# Connectors_MILSPEC.net
KiCad netlist of a schematic drawn in Altium Designer
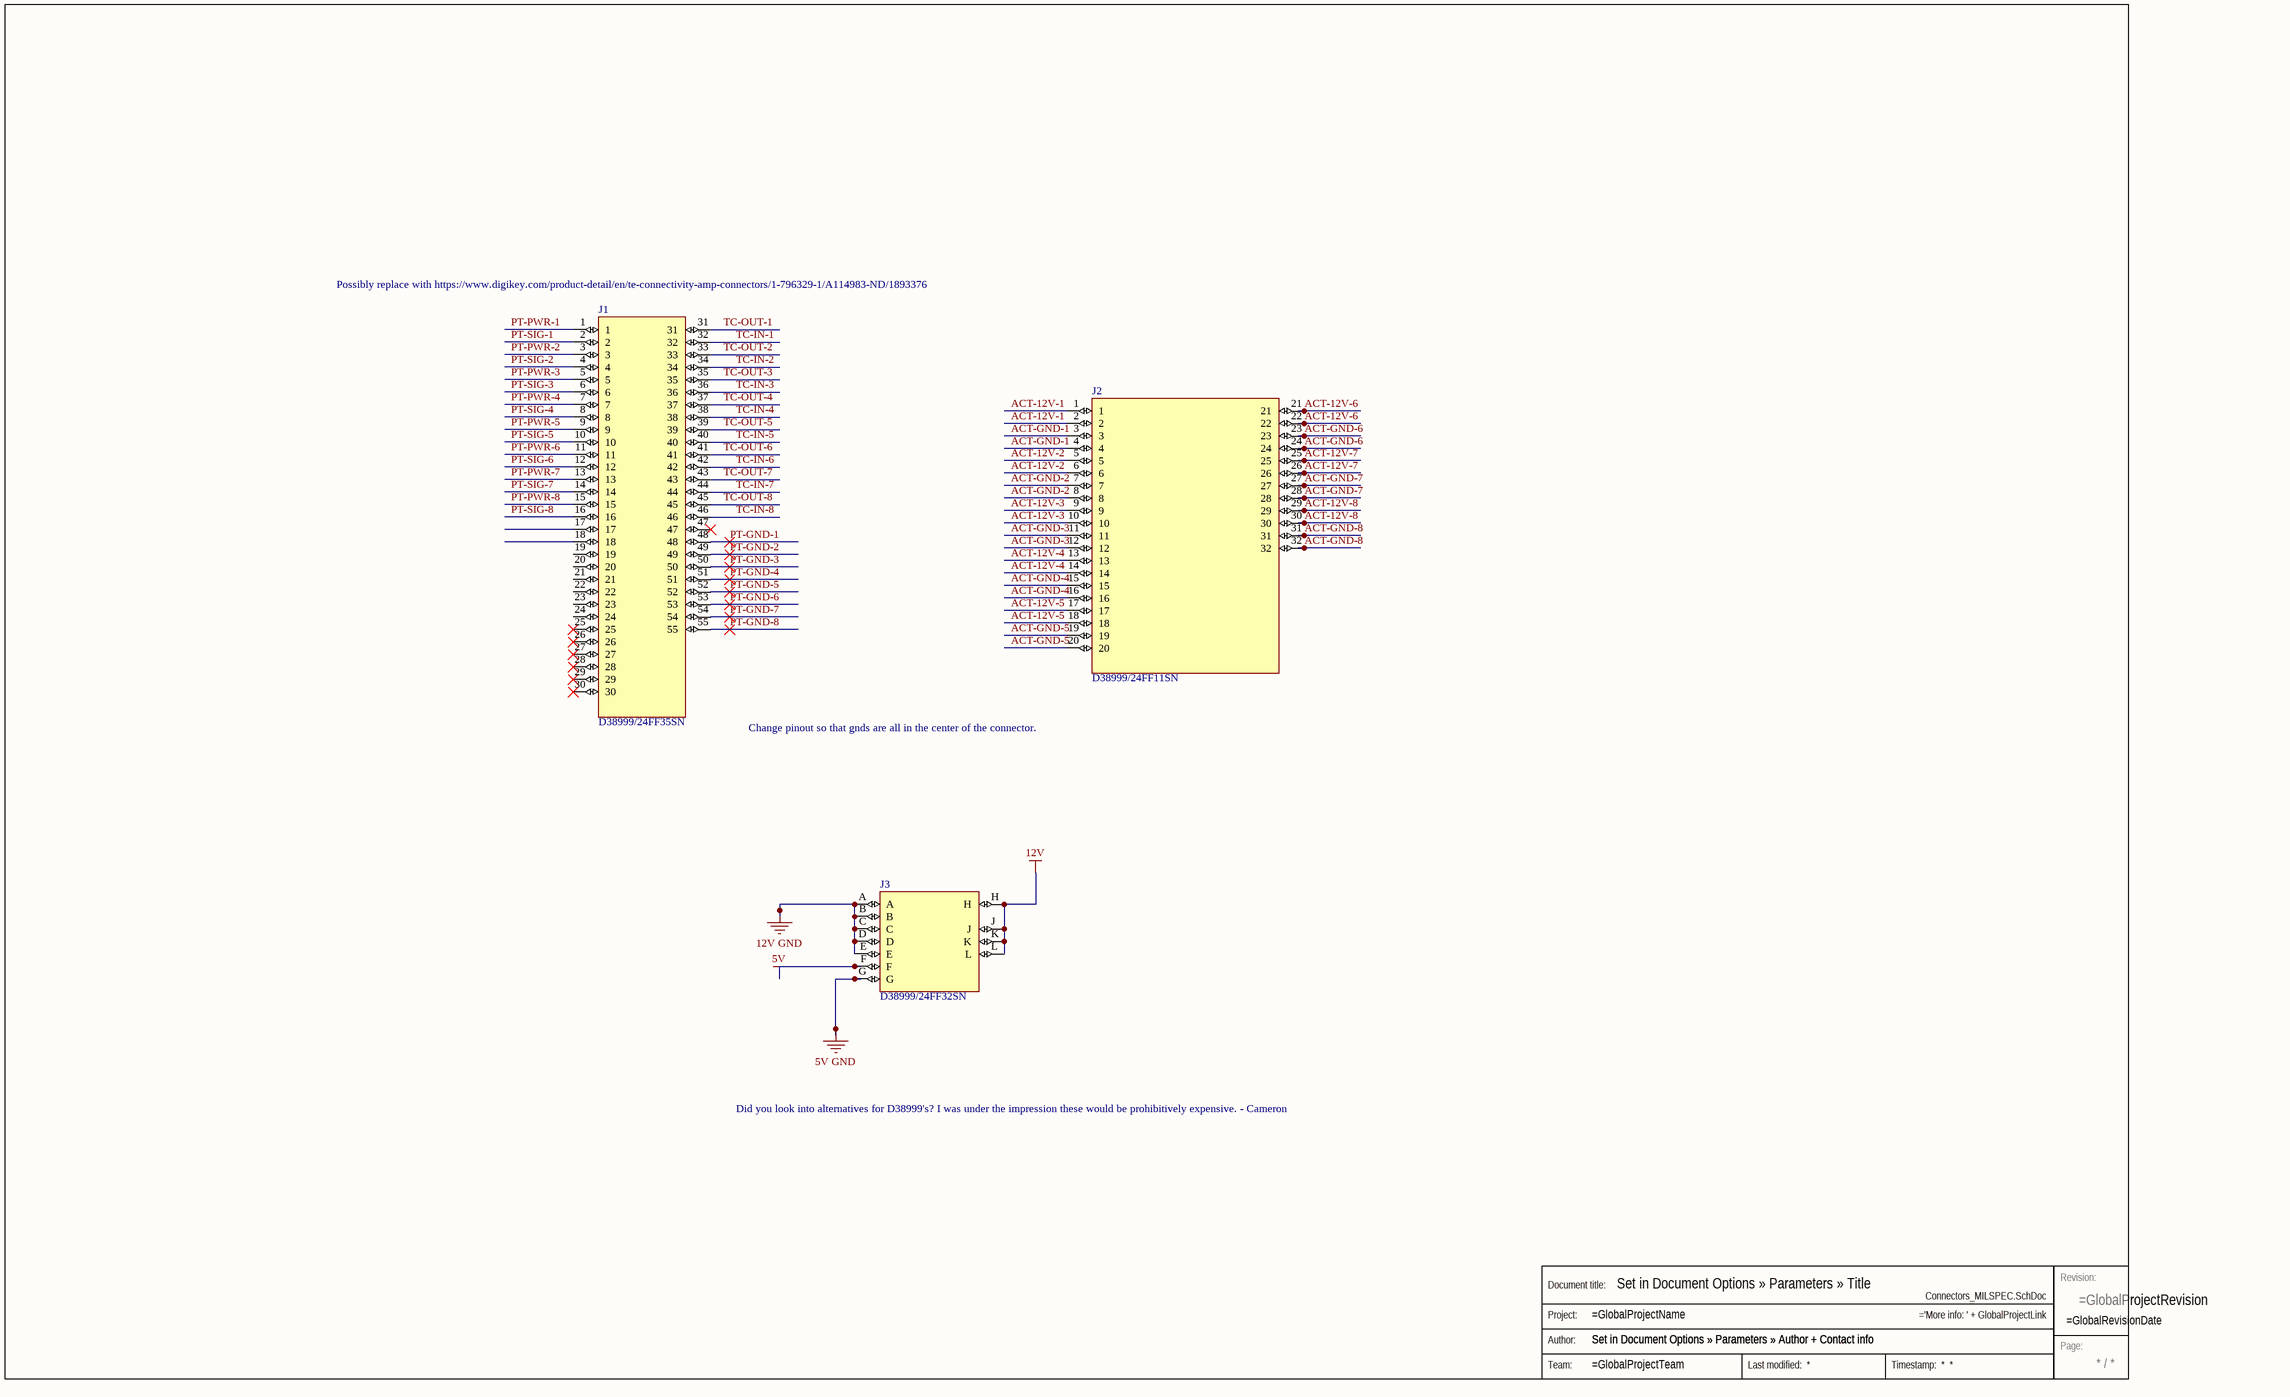
[diagram p0: Connectors_MILSPEC.SchDoc]

(export (version "E")
  (design (tool "Eeschema 10.0.6"))
  (components
    (comp (ref "J1")
      (value "D38999/24FF35SN")
      (footprint "17-35")
      (description "D38999/24FE35SN")
      (libsource (lib "D38999 connectors") (part "D38999/24FF35SN"))
    )
    (comp (ref "J2")
      (value "D38999/24FF11SN")
      (footprint "19-32")
      (libsource (lib "D38999 connectors") (part "D38999/24FF11SN"))
    )
    (comp (ref "J3")
      (value "D38999/24FF32SN")
      (footprint "19-11")
      (libsource (lib "D38999 connectors") (part "D38999/24FF32SN"))
    )
    (comp (ref "Stamp") (value "Stamp") (libsource (lib "ShieldsLib") (part "Stamp")))
  )
  (nets
    (net (code "1") (name "/ACT-12V-1") (class "Default")
      (node (ref "J2") (pin "1") (pinfunction "1_1") (pintype "bidirectional"))
      (node (ref "J2") (pin "2") (pinfunction "2_2") (pintype "bidirectional"))
    )
    (net (code "2") (name "/ACT-12V-2") (class "Default")
      (node (ref "J2") (pin "5") (pinfunction "5_5") (pintype "bidirectional"))
      (node (ref "J2") (pin "6") (pinfunction "6_6") (pintype "bidirectional"))
    )
    (net (code "3") (name "/ACT-12V-3") (class "Default")
      (node (ref "J2") (pin "10") (pinfunction "10_10") (pintype "bidirectional"))
      (node (ref "J2") (pin "9") (pinfunction "9_9") (pintype "bidirectional"))
    )
    (net (code "4") (name "/ACT-12V-4") (class "Default")
      (node (ref "J2") (pin "13") (pinfunction "13_13") (pintype "bidirectional"))
      (node (ref "J2") (pin "14") (pinfunction "14_14") (pintype "bidirectional"))
    )
    (net (code "5") (name "/ACT-12V-5") (class "Default")
      (node (ref "J2") (pin "17") (pinfunction "17_17") (pintype "bidirectional"))
      (node (ref "J2") (pin "18") (pinfunction "18_18") (pintype "bidirectional"))
    )
    (net (code "6") (name "/ACT-12V-6") (class "Default")
      (node (ref "J2") (pin "21") (pinfunction "21_21") (pintype "bidirectional"))
      (node (ref "J2") (pin "22") (pinfunction "22_22") (pintype "bidirectional"))
    )
    (net (code "7") (name "/ACT-12V-7") (class "Default")
      (node (ref "J2") (pin "25") (pinfunction "25_25") (pintype "bidirectional"))
      (node (ref "J2") (pin "26") (pinfunction "26_26") (pintype "bidirectional"))
    )
    (net (code "8") (name "/ACT-12V-8") (class "Default")
      (node (ref "J2") (pin "29") (pinfunction "29_29") (pintype "bidirectional"))
      (node (ref "J2") (pin "30") (pinfunction "30_30") (pintype "bidirectional"))
    )
    (net (code "9") (name "/ACT-GND-1") (class "Default")
      (node (ref "J2") (pin "3") (pinfunction "3_3") (pintype "bidirectional"))
      (node (ref "J2") (pin "4") (pinfunction "4_4") (pintype "bidirectional"))
    )
    (net (code "10") (name "/ACT-GND-2") (class "Default")
      (node (ref "J2") (pin "7") (pinfunction "7_7") (pintype "bidirectional"))
      (node (ref "J2") (pin "8") (pinfunction "8_8") (pintype "bidirectional"))
    )
    (net (code "11") (name "/ACT-GND-3") (class "Default")
      (node (ref "J2") (pin "11") (pinfunction "11_11") (pintype "bidirectional"))
      (node (ref "J2") (pin "12") (pinfunction "12_12") (pintype "bidirectional"))
    )
    (net (code "12") (name "/ACT-GND-4") (class "Default")
      (node (ref "J2") (pin "15") (pinfunction "15_15") (pintype "bidirectional"))
      (node (ref "J2") (pin "16") (pinfunction "16_16") (pintype "bidirectional"))
    )
    (net (code "13") (name "/ACT-GND-5") (class "Default")
      (node (ref "J2") (pin "19") (pinfunction "19_19") (pintype "bidirectional"))
      (node (ref "J2") (pin "20") (pinfunction "20_20") (pintype "bidirectional"))
    )
    (net (code "14") (name "/ACT-GND-6") (class "Default")
      (node (ref "J2") (pin "23") (pinfunction "23_23") (pintype "bidirectional"))
      (node (ref "J2") (pin "24") (pinfunction "24_24") (pintype "bidirectional"))
    )
    (net (code "15") (name "/ACT-GND-7") (class "Default")
      (node (ref "J2") (pin "27") (pinfunction "27_27") (pintype "bidirectional"))
      (node (ref "J2") (pin "28") (pinfunction "28_28") (pintype "bidirectional"))
    )
    (net (code "16") (name "/ACT-GND-8") (class "Default")
      (node (ref "J2") (pin "31") (pinfunction "31_31") (pintype "bidirectional"))
      (node (ref "J2") (pin "32") (pinfunction "32_32") (pintype "bidirectional"))
    )
    (net (code "25") (name "/PT-GND-1") (class "Default")
      (node (ref "J1") (pin "48") (pinfunction "48_48") (pintype "bidirectional"))
    )
    (net (code "26") (name "/PT-GND-2") (class "Default")
      (node (ref "J1") (pin "49") (pinfunction "49_49") (pintype "bidirectional"))
    )
    (net (code "27") (name "/PT-GND-3") (class "Default")
      (node (ref "J1") (pin "50") (pinfunction "50_50") (pintype "bidirectional"))
    )
    (net (code "28") (name "/PT-GND-4") (class "Default")
      (node (ref "J1") (pin "51") (pinfunction "51_51") (pintype "bidirectional"))
    )
    (net (code "29") (name "/PT-GND-5") (class "Default")
      (node (ref "J1") (pin "52") (pinfunction "52_52") (pintype "bidirectional"))
    )
    (net (code "30") (name "/PT-GND-6") (class "Default")
      (node (ref "J1") (pin "53") (pinfunction "53_53") (pintype "bidirectional"))
    )
    (net (code "31") (name "/PT-GND-7") (class "Default")
      (node (ref "J1") (pin "54") (pinfunction "54_54") (pintype "bidirectional"))
    )
    (net (code "32") (name "/PT-GND-8") (class "Default")
      (node (ref "J1") (pin "55") (pinfunction "55_55") (pintype "bidirectional"))
    )
    (net (code "33") (name "/PT-PWR-1") (class "Default")
      (node (ref "J1") (pin "1") (pinfunction "1_1") (pintype "bidirectional"))
    )
    (net (code "34") (name "/PT-PWR-2") (class "Default")
      (node (ref "J1") (pin "3") (pinfunction "3_3") (pintype "bidirectional"))
    )
    (net (code "35") (name "/PT-PWR-3") (class "Default")
      (node (ref "J1") (pin "5") (pinfunction "5_5") (pintype "bidirectional"))
    )
    (net (code "36") (name "/PT-PWR-4") (class "Default")
      (node (ref "J1") (pin "7") (pinfunction "7_7") (pintype "bidirectional"))
    )
    (net (code "37") (name "/PT-PWR-5") (class "Default")
      (node (ref "J1") (pin "9") (pinfunction "9_9") (pintype "bidirectional"))
    )
    (net (code "38") (name "/PT-PWR-6") (class "Default")
      (node (ref "J1") (pin "11") (pinfunction "11_11") (pintype "bidirectional"))
    )
    (net (code "39") (name "/PT-PWR-7") (class "Default")
      (node (ref "J1") (pin "13") (pinfunction "13_13") (pintype "bidirectional"))
    )
    (net (code "40") (name "/PT-PWR-8") (class "Default")
      (node (ref "J1") (pin "15") (pinfunction "15_15") (pintype "bidirectional"))
    )
    (net (code "41") (name "/PT-SIG-1") (class "Default")
      (node (ref "J1") (pin "2") (pinfunction "2_2") (pintype "bidirectional"))
    )
    (net (code "42") (name "/PT-SIG-2") (class "Default")
      (node (ref "J1") (pin "4") (pinfunction "4_4") (pintype "bidirectional"))
    )
    (net (code "43") (name "/PT-SIG-3") (class "Default")
      (node (ref "J1") (pin "6") (pinfunction "6_6") (pintype "bidirectional"))
    )
    (net (code "44") (name "/PT-SIG-4") (class "Default")
      (node (ref "J1") (pin "8") (pinfunction "8_8") (pintype "bidirectional"))
    )
    (net (code "45") (name "/PT-SIG-5") (class "Default")
      (node (ref "J1") (pin "10") (pinfunction "10_10") (pintype "bidirectional"))
    )
    (net (code "46") (name "/PT-SIG-6") (class "Default")
      (node (ref "J1") (pin "12") (pinfunction "12_12") (pintype "bidirectional"))
    )
    (net (code "47") (name "/PT-SIG-7") (class "Default")
      (node (ref "J1") (pin "14") (pinfunction "14_14") (pintype "bidirectional"))
    )
    (net (code "48") (name "/PT-SIG-8") (class "Default")
      (node (ref "J1") (pin "16") (pinfunction "16_16") (pintype "bidirectional"))
    )
    (net (code "49") (name "/TC-IN-1") (class "Default")
      (node (ref "J1") (pin "32") (pinfunction "32_32") (pintype "bidirectional"))
    )
    (net (code "50") (name "/TC-IN-2") (class "Default")
      (node (ref "J1") (pin "34") (pinfunction "34_34") (pintype "bidirectional"))
    )
    (net (code "51") (name "/TC-IN-3") (class "Default")
      (node (ref "J1") (pin "36") (pinfunction "36_36") (pintype "bidirectional"))
    )
    (net (code "52") (name "/TC-IN-4") (class "Default")
      (node (ref "J1") (pin "38") (pinfunction "38_38") (pintype "bidirectional"))
    )
    (net (code "53") (name "/TC-IN-5") (class "Default")
      (node (ref "J1") (pin "40") (pinfunction "40_40") (pintype "bidirectional"))
    )
    (net (code "54") (name "/TC-IN-6") (class "Default")
      (node (ref "J1") (pin "42") (pinfunction "42_42") (pintype "bidirectional"))
    )
    (net (code "55") (name "/TC-IN-7") (class "Default")
      (node (ref "J1") (pin "44") (pinfunction "44_44") (pintype "bidirectional"))
    )
    (net (code "56") (name "/TC-IN-8") (class "Default")
      (node (ref "J1") (pin "46") (pinfunction "46_46") (pintype "bidirectional"))
    )
    (net (code "57") (name "/TC-OUT-1") (class "Default")
      (node (ref "J1") (pin "31") (pinfunction "31_31") (pintype "bidirectional"))
    )
    (net (code "58") (name "/TC-OUT-2") (class "Default")
      (node (ref "J1") (pin "33") (pinfunction "33_33") (pintype "bidirectional"))
    )
    (net (code "59") (name "/TC-OUT-3") (class "Default")
      (node (ref "J1") (pin "35") (pinfunction "35_35") (pintype "bidirectional"))
    )
    (net (code "60") (name "/TC-OUT-4") (class "Default")
      (node (ref "J1") (pin "37") (pinfunction "37_37") (pintype "bidirectional"))
    )
    (net (code "61") (name "/TC-OUT-5") (class "Default")
      (node (ref "J1") (pin "39") (pinfunction "39_39") (pintype "bidirectional"))
    )
    (net (code "62") (name "/TC-OUT-6") (class "Default")
      (node (ref "J1") (pin "41") (pinfunction "41_41") (pintype "bidirectional"))
    )
    (net (code "63") (name "/TC-OUT-7") (class "Default")
      (node (ref "J1") (pin "43") (pinfunction "43_43") (pintype "bidirectional"))
    )
    (net (code "64") (name "/TC-OUT-8") (class "Default")
      (node (ref "J1") (pin "45") (pinfunction "45_45") (pintype "bidirectional"))
    )
    (net (code "65") (name "5V") (class "Default")
      (node (ref "J3") (pin "F") (pinfunction "F_F") (pintype "bidirectional"))
    )
    (net (code "66") (name "5V GND") (class "Default")
      (node (ref "J3") (pin "G") (pinfunction "G_G") (pintype "bidirectional"))
    )
    (net (code "67") (name "12V") (class "Default")
      (node (ref "J3") (pin "H") (pinfunction "H_H") (pintype "bidirectional"))
      (node (ref "J3") (pin "J") (pinfunction "J_J") (pintype "bidirectional"))
      (node (ref "J3") (pin "K") (pinfunction "K_K") (pintype "bidirectional"))
      (node (ref "J3") (pin "L") (pinfunction "L_L") (pintype "bidirectional"))
    )
    (net (code "68") (name "12V GND") (class "Default")
      (node (ref "J3") (pin "A") (pinfunction "A_A") (pintype "bidirectional"))
      (node (ref "J3") (pin "B") (pinfunction "B_B") (pintype "bidirectional"))
      (node (ref "J3") (pin "C") (pinfunction "C_C") (pintype "bidirectional"))
      (node (ref "J3") (pin "D") (pinfunction "D_D") (pintype "bidirectional"))
      (node (ref "J3") (pin "E") (pinfunction "E_E") (pintype "bidirectional"))
    )
    (net (code "69") (name "unconnected-(J1-Pad17)") (class "Default")
      (node (ref "J1") (pin "17") (pinfunction "17_17") (pintype "bidirectional"))
    )
    (net (code "70") (name "unconnected-(J1-Pad18)") (class "Default")
      (node (ref "J1") (pin "18") (pinfunction "18_18") (pintype "bidirectional"))
    )
    (net (code "71") (name "unconnected-(J1-Pad19)") (class "Default")
      (node (ref "J1") (pin "19") (pinfunction "19_19") (pintype "bidirectional"))
    )
    (net (code "72") (name "unconnected-(J1-Pad20)") (class "Default")
      (node (ref "J1") (pin "20") (pinfunction "20_20") (pintype "bidirectional"))
    )
    (net (code "73") (name "unconnected-(J1-Pad21)") (class "Default")
      (node (ref "J1") (pin "21") (pinfunction "21_21") (pintype "bidirectional"))
    )
    (net (code "74") (name "unconnected-(J1-Pad22)") (class "Default")
      (node (ref "J1") (pin "22") (pinfunction "22_22") (pintype "bidirectional"))
    )
    (net (code "75") (name "unconnected-(J1-Pad23)") (class "Default")
      (node (ref "J1") (pin "23") (pinfunction "23_23") (pintype "bidirectional"))
    )
    (net (code "76") (name "unconnected-(J1-Pad24)") (class "Default")
      (node (ref "J1") (pin "24") (pinfunction "24_24") (pintype "bidirectional"))
    )
    (net (code "77") (name "unconnected-(J1-Pad25)") (class "Default")
      (node (ref "J1") (pin "25") (pinfunction "25_25") (pintype "bidirectional+no_connect"))
    )
    (net (code "78") (name "unconnected-(J1-Pad26)") (class "Default")
      (node (ref "J1") (pin "26") (pinfunction "26_26") (pintype "bidirectional+no_connect"))
    )
    (net (code "79") (name "unconnected-(J1-Pad27)") (class "Default")
      (node (ref "J1") (pin "27") (pinfunction "27_27") (pintype "bidirectional+no_connect"))
    )
    (net (code "80") (name "unconnected-(J1-Pad28)") (class "Default")
      (node (ref "J1") (pin "28") (pinfunction "28_28") (pintype "bidirectional+no_connect"))
    )
    (net (code "81") (name "unconnected-(J1-Pad29)") (class "Default")
      (node (ref "J1") (pin "29") (pinfunction "29_29") (pintype "bidirectional+no_connect"))
    )
    (net (code "82") (name "unconnected-(J1-Pad30)") (class "Default")
      (node (ref "J1") (pin "30") (pinfunction "30_30") (pintype "bidirectional+no_connect"))
    )
    (net (code "83") (name "unconnected-(J1-Pad47)") (class "Default")
      (node (ref "J1") (pin "47") (pinfunction "47_47") (pintype "bidirectional+no_connect"))
    )
  )
)
